# Sheet3.net
KiCad netlist of a schematic drawn in Altium Designer
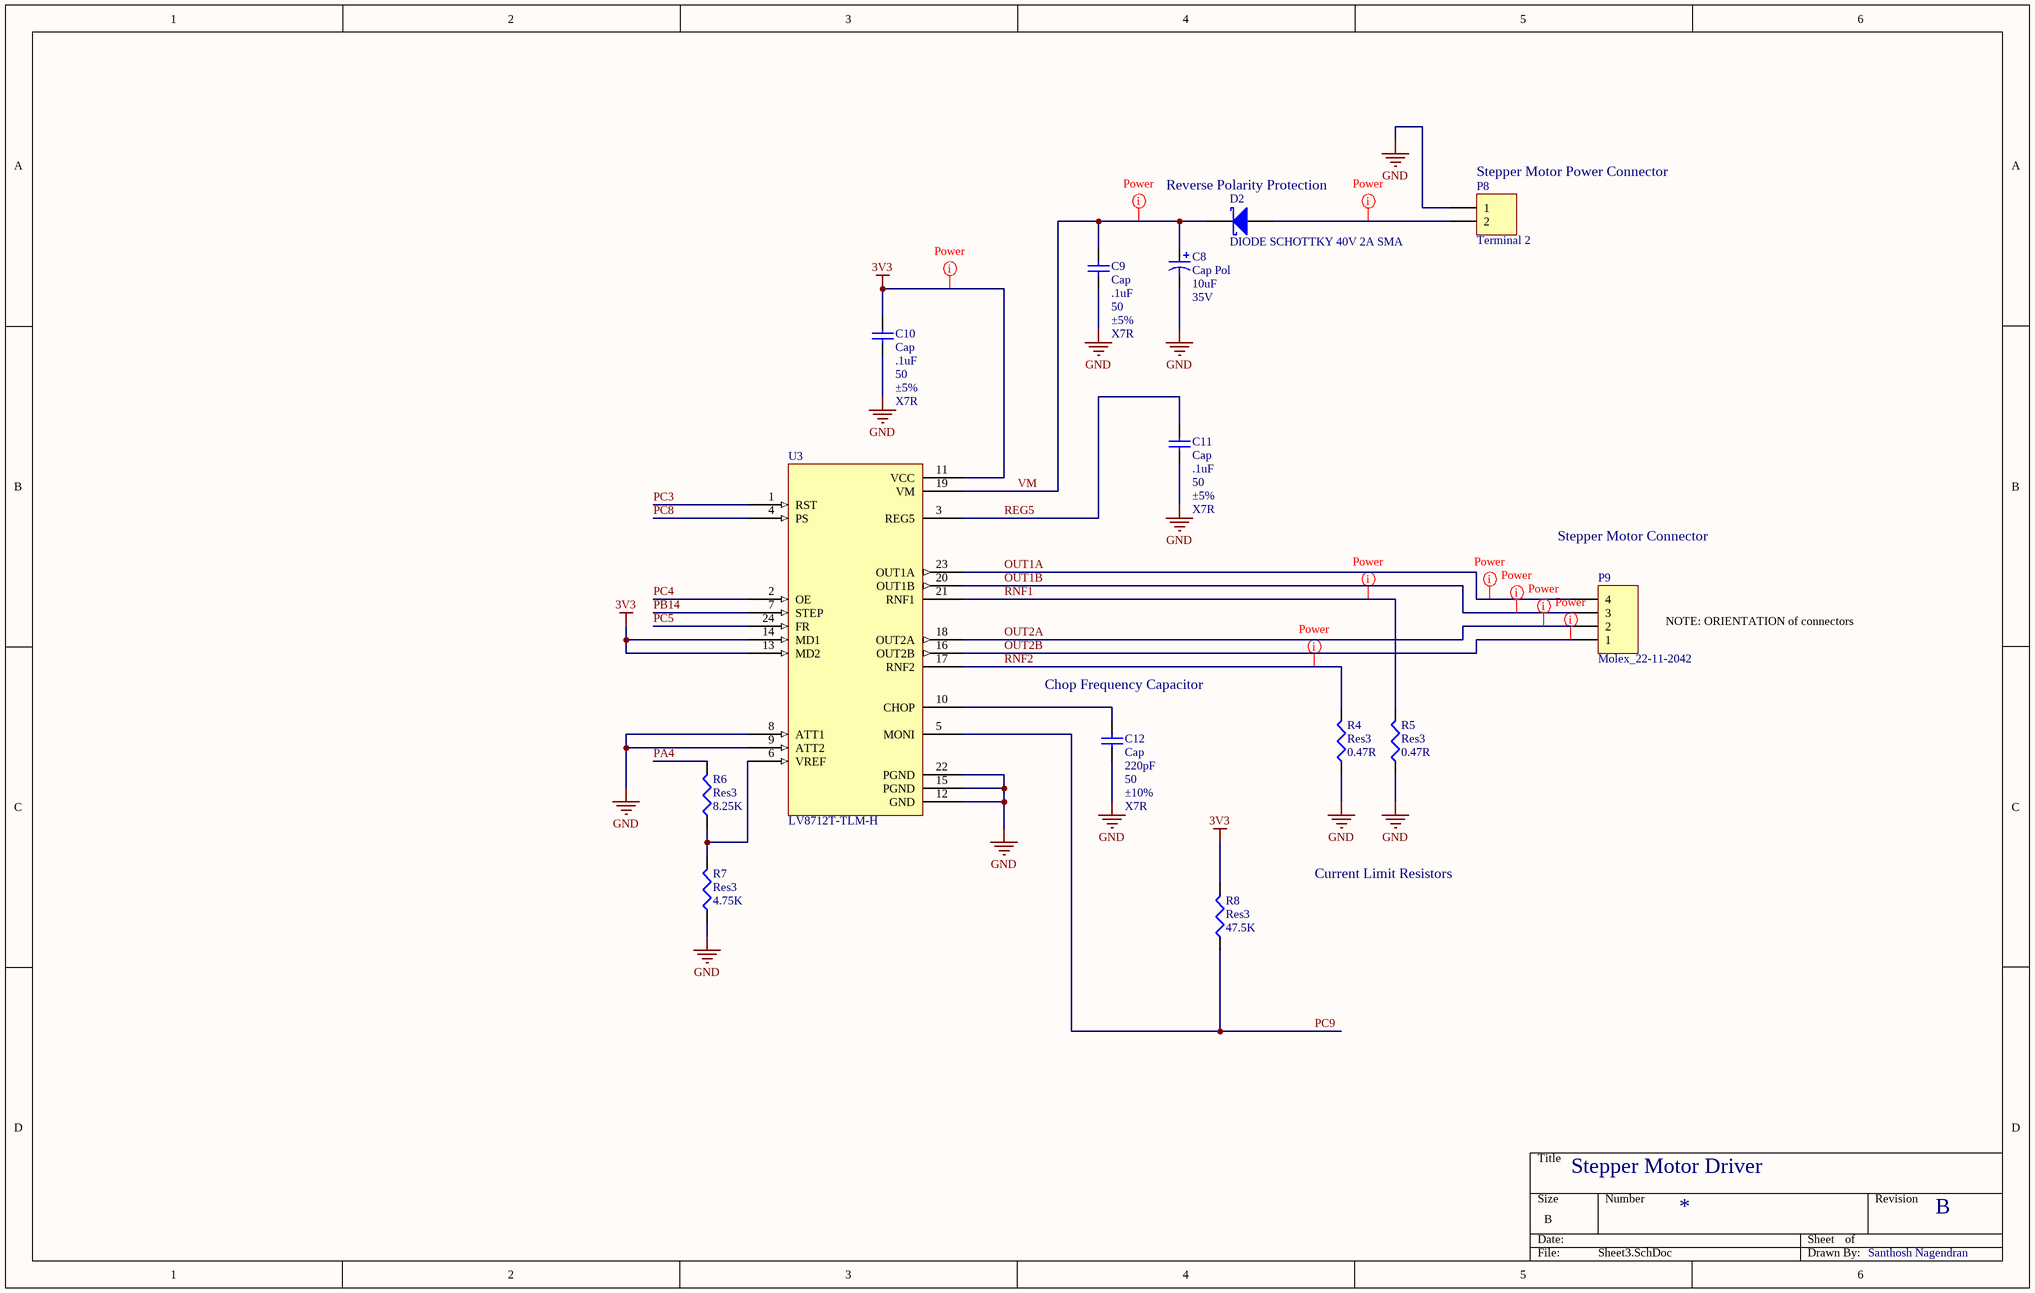
[diagram p0: Sheet3.SchDoc]

(export (version "E")
  (design (tool "Eeschema 10.0.6"))
  (components
    (comp (ref "C8")
      (value "Cap Pol")
      (footprint "CAPACITOR_5MM")
      (description "CAP 85C 10uF ±20% 35V WX Series Aluminum Electrolytic")
      (fields
        (field (name "ALTIUM_VALUE") "10uF")
        (field (name "VOLTAGE") "35V")
        (field (name "MPN") "UWX1V100MCL1GB")
      )
      (libsource (lib "esd_library") (part "Cap Polar-10uF-35V"))
    )
    (comp (ref "C9")
      (value "Cap")
      (footprint "CAPC2012X09M")
      (description "CAP CER .1uF 50v X7R 0805")
      (fields
        (field (name "ALTIUM_VALUE") ".1uF")
        (field (name "WV") "50")
        (field (name "TOLERANCE") "±5%")
        (field (name "TYPE") "X7R")
        (field (name "MPN") "C0805C104J5RACTU")
      )
      (libsource (lib "esd_library") (part "CAP-X7R-.1uF-50V-±5%"))
    )
    (comp (ref "C10")
      (value "Cap")
      (footprint "CAPC2012X09M")
      (description "CAP CER .1uF 50v X7R 0805")
      (fields
        (field (name "ALTIUM_VALUE") ".1uF")
        (field (name "WV") "50")
        (field (name "TOLERANCE") "±5%")
        (field (name "TYPE") "X7R")
        (field (name "MPN") "C0805C104J5RACTU")
      )
      (libsource (lib "esd_library") (part "CAP-X7R-.1uF-50V-±5%"))
    )
    (comp (ref "C11")
      (value "Cap")
      (footprint "CAPC2012X09M")
      (description "CAP CER .1uF 50v X7R 0805")
      (fields
        (field (name "ALTIUM_VALUE") ".1uF")
        (field (name "WV") "50")
        (field (name "TOLERANCE") "±5%")
        (field (name "TYPE") "X7R")
        (field (name "MPN") "C0805C104J5RACTU")
      )
      (libsource (lib "esd_library") (part "CAP-X7R-.1uF-50V-±5%"))
    )
    (comp (ref "C12")
      (value "Cap")
      (footprint "CAPC2012X09M")
      (description "CAP CER 220pF 50v X7R 0805")
      (fields
        (field (name "ALTIUM_VALUE") "220pF")
        (field (name "WV") "50")
        (field (name "TOLERANCE") "±10%")
        (field (name "TYPE") "X7R")
        (field (name "MPN") "C0805C221K5RACTU")
      )
      (libsource (lib "esd_library") (part "CAP-X7R-220pF-50V-±10%"))
    )
    (comp (ref "D2")
      (value "DIODE SCHOTTKY 40V 2A SMA")
      (footprint "DIOM4326X23M")
      (description "Schottky Rectifier")
      (fields (field (name "MPN") "B240A-13-F"))
      (libsource (lib "esd_library") (part "DIODE SCHOTTKY 40V 2A SMA"))
    )
    (comp (ref "P8")
      (value "Terminal 2")
      (footprint "TYCO_282841_2")
      (description "Terminal, 2-Pin")
      (fields (field (name "MPN") "282841-2") (field (name "PUBLISHER") "Altium Limited"))
      (libsource (lib "esd_library") (part "Terminal 2"))
    )
    (comp (ref "P9")
      (value "Molex_22-11-2042")
      (footprint "MOLEX-22-11-2042")
      (description "CONN HEADER 4POS .100 VERT GOLD")
      (fields (field (name "MPN") "0022112042"))
      (libsource (lib "esd_library") (part "Molex_22-11-2042"))
    )
    (comp (ref "R4")
      (value "Res3")
      (footprint "RESC3125X07M")
      (description "RES SMD 0.47OHM 5% 1W 1210")
      (fields (field (name "MPN") "RCWE1210R470FKEA") (field (name "ALTIUM_VALUE") "0.47R"))
      (libsource (lib "esd_library") (part "Resistor_0.47R_1W"))
    )
    (comp (ref "R5")
      (value "Res3")
      (footprint "RESC3125X07M")
      (description "RES SMD 0.47OHM 5% 1W 1210")
      (fields (field (name "MPN") "RCWE1210R470FKEA") (field (name "ALTIUM_VALUE") "0.47R"))
      (libsource (lib "esd_library") (part "Resistor_0.47R_1W"))
    )
    (comp (ref "R6")
      (value "Res3")
      (footprint "RESC2112X05M")
      (description "RES SMD 8.25K OHM 1% 1/8W 0805")
      (fields (field (name "ALTIUM_VALUE") "8.25K") (field (name "MPN") "CRCW08058K25FKEA"))
      (libsource (lib "esd_library") (part "Resistor_8.25K"))
    )
    (comp (ref "R7")
      (value "Res3")
      (footprint "RESC2112X05M")
      (description "RES SMD 4.75K OHM 1% 1/8W 0805")
      (fields (field (name "ALTIUM_VALUE") "4.75K") (field (name "MPN") "CRCW08054K75FKEA"))
      (libsource (lib "esd_library") (part "Resistor_4.75K"))
    )
    (comp (ref "R8")
      (value "Res3")
      (footprint "RESC2112X05M")
      (description "RES SMD 47.5K OHM 1% 1/8W 0805")
      (fields (field (name "ALTIUM_VALUE") "47.5K") (field (name "MPN") "CRCW080547K5FKEA"))
      (libsource (lib "esd_library") (part "Resistor_47.5K"))
    )
    (comp (ref "U3")
      (value "LV8712T-TLM-H")
      (footprint "ONSEMITSSOP50P640X120-24M")
      (description "IC MOTOR DRIVER PAR 24TSSOP")
      (libsource (lib "esd_library") (part "LV8712T-TLM-H"))
    )
  )
  (nets
    (net (code "1") (name "/OUT1A") (class "Default")
      (node (ref "P9") (pin "4") (pinfunction "4_4") (pintype "passive"))
      (node (ref "U3") (pin "23") (pinfunction "OUT1A_23") (pintype "output"))
    )
    (net (code "2") (name "/OUT1B") (class "Default")
      (node (ref "P9") (pin "3") (pinfunction "3_3") (pintype "passive"))
      (node (ref "U3") (pin "20") (pinfunction "OUT1B_20") (pintype "output"))
    )
    (net (code "3") (name "/OUT2A") (class "Default")
      (node (ref "P9") (pin "2") (pinfunction "2_2") (pintype "passive"))
      (node (ref "U3") (pin "18") (pinfunction "OUT2A_18") (pintype "output"))
    )
    (net (code "4") (name "/OUT2B") (class "Default")
      (node (ref "P9") (pin "1") (pinfunction "1_1") (pintype "passive"))
      (node (ref "U3") (pin "16") (pinfunction "OUT2B_16") (pintype "output"))
    )
    (net (code "5") (name "/PA4") (class "Default")
      (node (ref "R6") (pin "2") (pinfunction "2_2") (pintype "passive"))
    )
    (net (code "6") (name "/PB14") (class "Default")
      (node (ref "U3") (pin "7") (pinfunction "STEP_7") (pintype "input"))
    )
    (net (code "7") (name "/PC3") (class "Default")
      (node (ref "U3") (pin "1") (pinfunction "RST_1") (pintype "input"))
    )
    (net (code "8") (name "/PC4") (class "Default")
      (node (ref "U3") (pin "2") (pinfunction "OE_2") (pintype "input"))
    )
    (net (code "9") (name "/PC5") (class "Default")
      (node (ref "U3") (pin "24") (pinfunction "FR_24") (pintype "input"))
    )
    (net (code "10") (name "/PC8") (class "Default")
      (node (ref "U3") (pin "4") (pinfunction "PS_4") (pintype "input"))
    )
    (net (code "11") (name "/PC9") (class "Default")
      (node (ref "R8") (pin "1") (pinfunction "1_1") (pintype "passive"))
      (node (ref "U3") (pin "5") (pinfunction "MONI_5") (pintype "open_collector"))
    )
    (net (code "12") (name "/REG5") (class "Default")
      (node (ref "C11") (pin "2") (pinfunction "2_2") (pintype "passive"))
      (node (ref "U3") (pin "3") (pinfunction "REG5_3") (pintype "power_in"))
    )
    (net (code "13") (name "/RNF1") (class "Default")
      (node (ref "R5") (pin "2") (pinfunction "2_2") (pintype "passive"))
      (node (ref "U3") (pin "21") (pinfunction "RNF1_21") (pintype "passive"))
    )
    (net (code "14") (name "/RNF2") (class "Default")
      (node (ref "R4") (pin "2") (pinfunction "2_2") (pintype "passive"))
      (node (ref "U3") (pin "17") (pinfunction "RNF2_17") (pintype "passive"))
    )
    (net (code "15") (name "/VM") (class "Default")
      (node (ref "C8") (pin "1") (pinfunction "1_1") (pintype "passive"))
      (node (ref "C9") (pin "2") (pinfunction "2_2") (pintype "passive"))
      (node (ref "D2") (pin "1") (pinfunction "K_1") (pintype "passive"))
      (node (ref "U3") (pin "19") (pinfunction "VM_19") (pintype "power_in"))
    )
    (net (code "16") (name "3V3") (class "Default")
      (node (ref "C10") (pin "2") (pinfunction "2_2") (pintype "passive"))
      (node (ref "R8") (pin "2") (pinfunction "2_2") (pintype "passive"))
      (node (ref "U3") (pin "11") (pinfunction "VCC_11") (pintype "power_in"))
      (node (ref "U3") (pin "13") (pinfunction "MD2_13") (pintype "input"))
      (node (ref "U3") (pin "14") (pinfunction "MD1_14") (pintype "input"))
    )
    (net (code "17") (name "GND") (class "Default")
      (node (ref "C10") (pin "1") (pinfunction "1_1") (pintype "passive"))
      (node (ref "C11") (pin "1") (pinfunction "1_1") (pintype "passive"))
      (node (ref "C12") (pin "1") (pinfunction "1_1") (pintype "passive"))
      (node (ref "C8") (pin "2") (pinfunction "2_2") (pintype "passive"))
      (node (ref "C9") (pin "1") (pinfunction "1_1") (pintype "passive"))
      (node (ref "P8") (pin "1") (pinfunction "1_1") (pintype "passive"))
      (node (ref "R4") (pin "1") (pinfunction "1_1") (pintype "passive"))
      (node (ref "R5") (pin "1") (pinfunction "1_1") (pintype "passive"))
      (node (ref "R7") (pin "1") (pinfunction "1_1") (pintype "passive"))
      (node (ref "U3") (pin "12") (pinfunction "GND_12") (pintype "power_in"))
      (node (ref "U3") (pin "15") (pinfunction "PGND_15") (pintype "power_in"))
      (node (ref "U3") (pin "22") (pinfunction "PGND_22") (pintype "power_in"))
      (node (ref "U3") (pin "8") (pinfunction "ATT1_8") (pintype "input"))
      (node (ref "U3") (pin "9") (pinfunction "ATT2_9") (pintype "input"))
    )
    (net (code "18") (name "Net-(D2-A)") (class "Default")
      (node (ref "D2") (pin "2") (pinfunction "A_2") (pintype "passive"))
      (node (ref "P8") (pin "2") (pinfunction "2_2") (pintype "passive"))
    )
    (net (code "19") (name "Net-(U3-CHOP)") (class "Default")
      (node (ref "C12") (pin "2") (pinfunction "2_2") (pintype "passive"))
      (node (ref "U3") (pin "10") (pinfunction "CHOP_10") (pintype "passive"))
    )
    (net (code "20") (name "Net-(U3-VREF)") (class "Default")
      (node (ref "R6") (pin "1") (pinfunction "1_1") (pintype "passive"))
      (node (ref "R7") (pin "2") (pinfunction "2_2") (pintype "passive"))
      (node (ref "U3") (pin "6") (pinfunction "VREF_6") (pintype "input"))
    )
  )
)
